# SmartBakerySensor.net
KiCad netlist of a schematic drawn in EAGLE
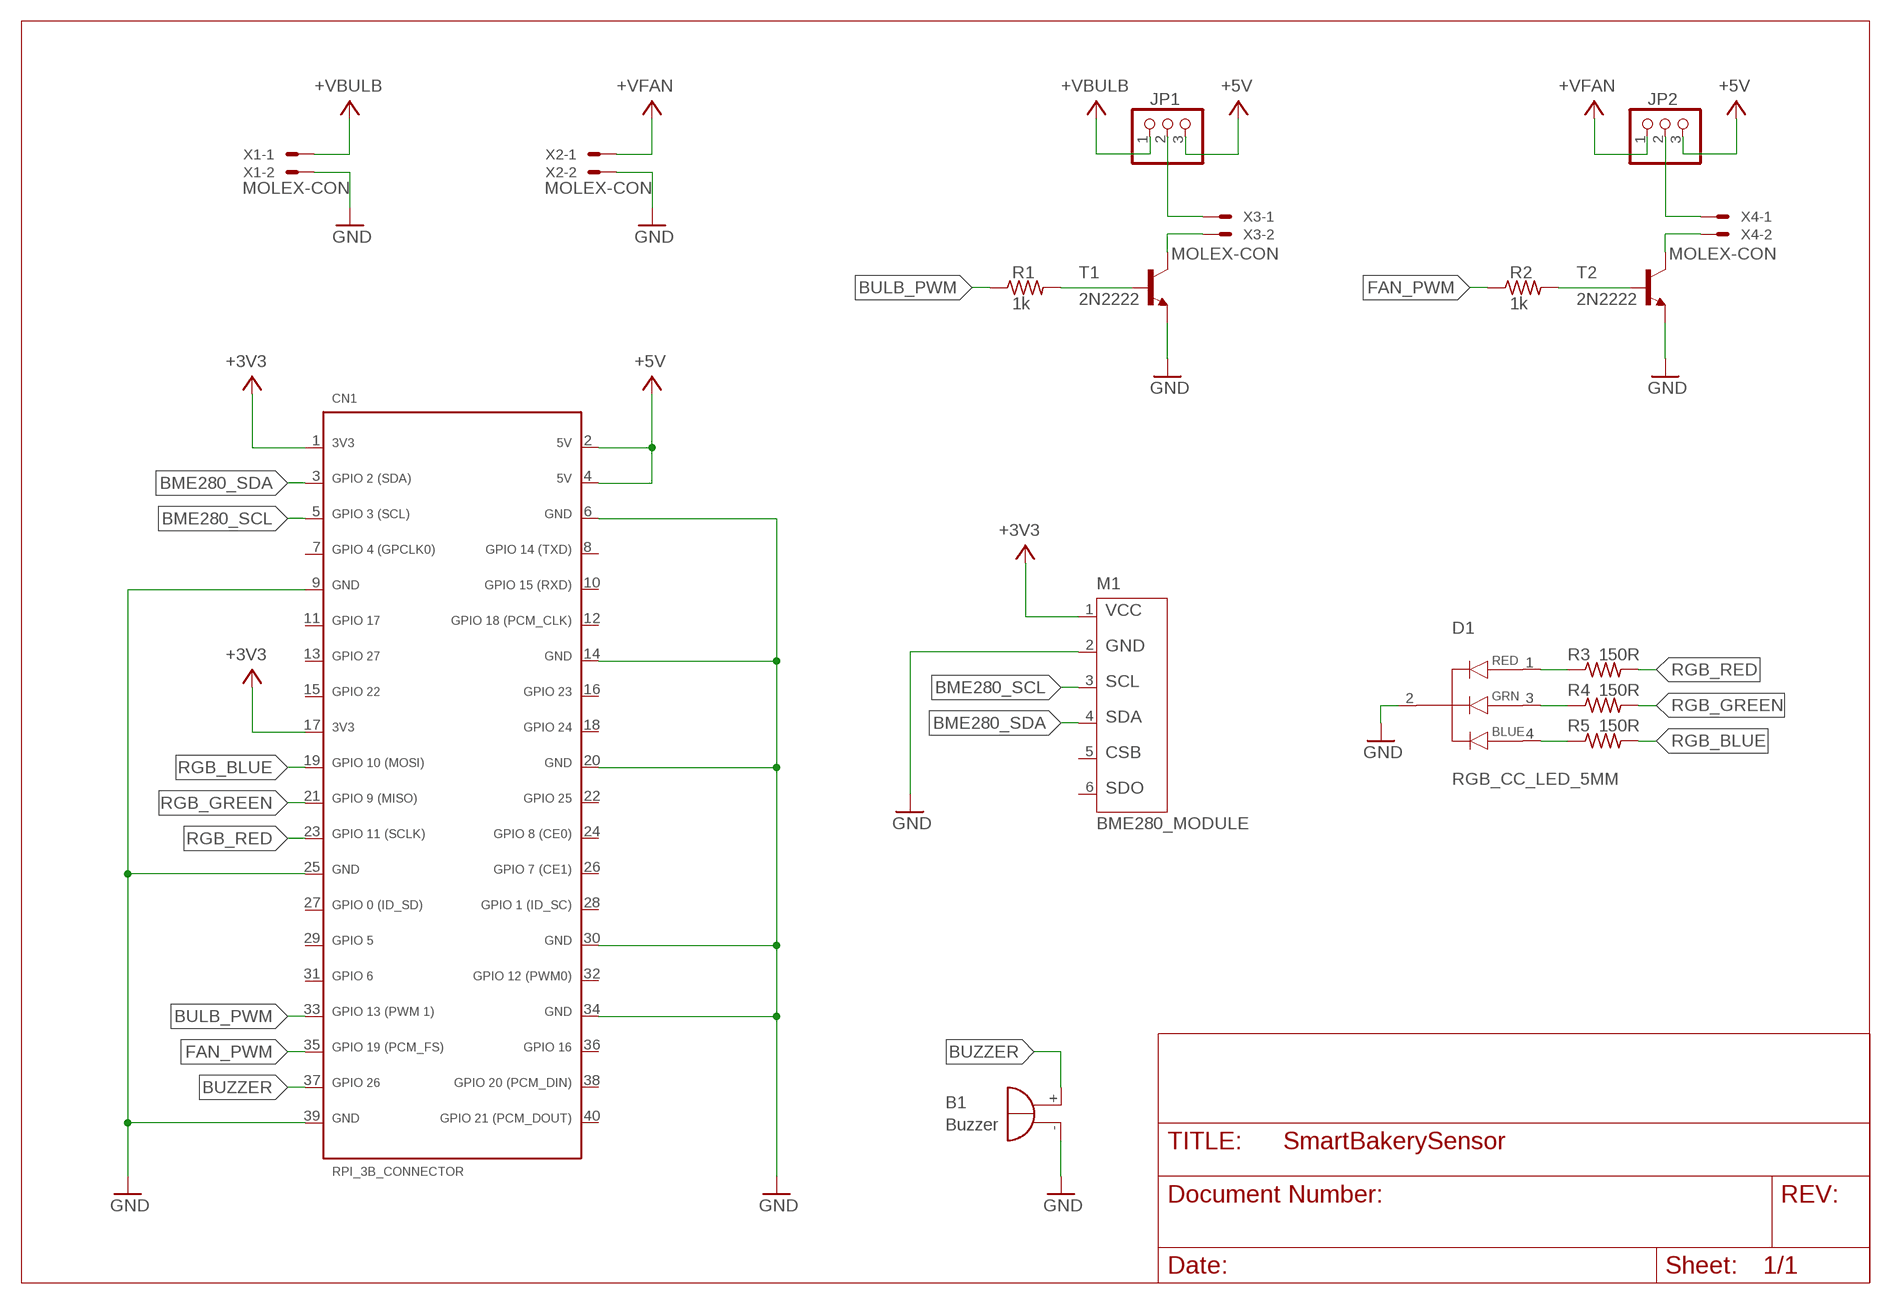
[diagram p0: schematic, sheet 1]

(export (version "E")
  (design (tool "Eeschema 10.0.6"))
  (components
    (comp (ref "B1")
      (value "Buzzer")
      (footprint "eagle-import:F_TMB")
      (libsource (lib "eagle-import") (part "F/TMB"))
    )
    (comp (ref "CN1")
      (value "RPI_3B_CONNECTOR")
      (footprint "eagle-import:RPI_3B_CONNECTOR_FOOTPRINT")
      (libsource (lib "eagle-import") (part "RPI_3B_CONNECTOR"))
    )
    (comp (ref "D1")
      (value "RGB_CC_LED_5MM")
      (footprint "eagle-import:RGB_CC_LED_FOOTPRINT")
      (libsource (lib "eagle-import") (part "RGB_CC_LED_5MM"))
    )
    (comp (ref "JP1")
      (value "PINHD-1X3")
      (footprint "eagle-import:1X03")
      (libsource (lib "eagle-import") (part "PINHD-1X3"))
    )
    (comp (ref "JP2")
      (value "PINHD-1X3")
      (footprint "eagle-import:1X03")
      (libsource (lib "eagle-import") (part "PINHD-1X3"))
    )
    (comp (ref "M1")
      (value "BME280_MODULE")
      (footprint "eagle-import:BME280_FOOTPRINT")
      (libsource (lib "eagle-import") (part "BME280_MODULE"))
    )
    (comp (ref "R1")
      (value "1k")
      (footprint "eagle-import:R0805")
      (libsource (lib "eagle-import") (part "R-US_R0805"))
    )
    (comp (ref "R2")
      (value "1k")
      (footprint "eagle-import:R0805")
      (libsource (lib "eagle-import") (part "R-US_R0805"))
    )
    (comp (ref "R3")
      (value "150R")
      (footprint "eagle-import:R0805")
      (libsource (lib "eagle-import") (part "R-US_R0805"))
    )
    (comp (ref "R4")
      (value "150R")
      (footprint "eagle-import:R0805")
      (libsource (lib "eagle-import") (part "R-US_R0805"))
    )
    (comp (ref "R5")
      (value "150R")
      (footprint "eagle-import:R0805")
      (libsource (lib "eagle-import") (part "R-US_R0805"))
    )
    (comp (ref "T1")
      (value "2N2222")
      (footprint "eagle-import:TO92-EBC")
      (libsource (lib "eagle-import") (part "-NPN-TO92-EBC2N2222"))
    )
    (comp (ref "T2")
      (value "2N2222")
      (footprint "eagle-import:TO92-EBC")
      (libsource (lib "eagle-import") (part "-NPN-TO92-EBC2N2222"))
    )
    (comp (ref "X1")
      (value "MOLEX-CON")
      (footprint "eagle-import:22-23-2021")
      (fields (field (name "MF") "MOLEX") (field (name "MPN") "22-23-2021"))
      (libsource (lib "eagle-import") (part "22-23-2021"))
    )
    (comp (ref "X2")
      (value "MOLEX-CON")
      (footprint "eagle-import:22-23-2021")
      (fields (field (name "MF") "MOLEX") (field (name "MPN") "22-23-2021"))
      (libsource (lib "eagle-import") (part "22-23-2021"))
    )
    (comp (ref "X3")
      (value "MOLEX-CON")
      (footprint "eagle-import:22-23-2021")
      (fields (field (name "MF") "MOLEX") (field (name "MPN") "22-23-2021"))
      (libsource (lib "eagle-import") (part "22-23-2021"))
    )
    (comp (ref "X4")
      (value "MOLEX-CON")
      (footprint "eagle-import:22-23-2021")
      (fields (field (name "MF") "MOLEX") (field (name "MPN") "22-23-2021"))
      (libsource (lib "eagle-import") (part "22-23-2021"))
    )
  )
  (nets
    (net (code "1") (name "+3V3") (class "Default")
      (node (ref "CN1") (pin "1") (pinfunction "1_1") (pintype "bidirectional"))
      (node (ref "CN1") (pin "17") (pinfunction "17_17") (pintype "bidirectional"))
      (node (ref "M1") (pin "1") (pinfunction "1_1") (pintype "bidirectional"))
    )
    (net (code "2") (name "+5V") (class "Default")
      (node (ref "CN1") (pin "2") (pinfunction "2_2") (pintype "bidirectional"))
      (node (ref "CN1") (pin "4") (pinfunction "4_4") (pintype "bidirectional"))
      (node (ref "JP1") (pin "3") (pinfunction "3_3") (pintype "passive"))
      (node (ref "JP2") (pin "3") (pinfunction "3_3") (pintype "passive"))
    )
    (net (code "3") (name "+VBULB") (class "Default")
      (node (ref "JP1") (pin "1") (pinfunction "1_1") (pintype "passive"))
      (node (ref "X1") (pin "1") (pinfunction "S_1") (pintype "passive"))
    )
    (net (code "4") (name "+VFAN") (class "Default")
      (node (ref "JP2") (pin "1") (pinfunction "1_1") (pintype "passive"))
      (node (ref "X2") (pin "1") (pinfunction "S_1") (pintype "passive"))
    )
    (net (code "5") (name "BME280_SCL") (class "Default")
      (node (ref "CN1") (pin "5") (pinfunction "5_5") (pintype "bidirectional"))
      (node (ref "M1") (pin "3") (pinfunction "3_3") (pintype "bidirectional"))
    )
    (net (code "6") (name "BME280_SDA") (class "Default")
      (node (ref "CN1") (pin "3") (pinfunction "3_3") (pintype "bidirectional"))
      (node (ref "M1") (pin "4") (pinfunction "4_4") (pintype "bidirectional"))
    )
    (net (code "7") (name "BULB_PWM") (class "Default")
      (node (ref "CN1") (pin "33") (pinfunction "33_33") (pintype "bidirectional"))
      (node (ref "R1") (pin "1") (pinfunction "1_1") (pintype "passive"))
    )
    (net (code "8") (name "BUZZER") (class "Default")
      (node (ref "B1") (pin "+") (pinfunction "+_+") (pintype "passive"))
      (node (ref "CN1") (pin "37") (pinfunction "37_37") (pintype "bidirectional"))
    )
    (net (code "9") (name "FAN_PWM") (class "Default")
      (node (ref "CN1") (pin "35") (pinfunction "35_35") (pintype "bidirectional"))
      (node (ref "R2") (pin "1") (pinfunction "1_1") (pintype "passive"))
    )
    (net (code "10") (name "GND") (class "Default")
      (node (ref "B1") (pin "-") (pinfunction "-_-") (pintype "passive"))
      (node (ref "CN1") (pin "14") (pinfunction "14_14") (pintype "bidirectional"))
      (node (ref "CN1") (pin "20") (pinfunction "20_20") (pintype "bidirectional"))
      (node (ref "CN1") (pin "25") (pinfunction "25_25") (pintype "bidirectional"))
      (node (ref "CN1") (pin "30") (pinfunction "30_30") (pintype "bidirectional"))
      (node (ref "CN1") (pin "34") (pinfunction "34_34") (pintype "bidirectional"))
      (node (ref "CN1") (pin "39") (pinfunction "39_39") (pintype "bidirectional"))
      (node (ref "CN1") (pin "6") (pinfunction "6_6") (pintype "bidirectional"))
      (node (ref "CN1") (pin "9") (pinfunction "9_9") (pintype "bidirectional"))
      (node (ref "D1") (pin "2") (pinfunction "2_2") (pintype "bidirectional"))
      (node (ref "M1") (pin "2") (pinfunction "2_2") (pintype "bidirectional"))
      (node (ref "T1") (pin "E") (pinfunction "E_E") (pintype "passive"))
      (node (ref "T2") (pin "E") (pinfunction "E_E") (pintype "passive"))
      (node (ref "X1") (pin "2") (pinfunction "S_2") (pintype "passive"))
      (node (ref "X2") (pin "2") (pinfunction "S_2") (pintype "passive"))
    )
    (net (code "11") (name "Net-(D1-Pad1)") (class "Default")
      (node (ref "D1") (pin "1") (pinfunction "1_1") (pintype "bidirectional"))
      (node (ref "R3") (pin "1") (pinfunction "1_1") (pintype "passive"))
    )
    (net (code "12") (name "Net-(D1-Pad3)") (class "Default")
      (node (ref "D1") (pin "3") (pinfunction "3_3") (pintype "bidirectional"))
      (node (ref "R4") (pin "1") (pinfunction "1_1") (pintype "passive"))
    )
    (net (code "13") (name "Net-(D1-Pad4)") (class "Default")
      (node (ref "D1") (pin "4") (pinfunction "4_4") (pintype "bidirectional"))
      (node (ref "R5") (pin "1") (pinfunction "1_1") (pintype "passive"))
    )
    (net (code "14") (name "Net-(R1-Pad2)") (class "Default")
      (node (ref "R1") (pin "2") (pinfunction "2_2") (pintype "passive"))
      (node (ref "T1") (pin "B") (pinfunction "B_B") (pintype "passive"))
    )
    (net (code "15") (name "Net-(R2-Pad2)") (class "Default")
      (node (ref "R2") (pin "2") (pinfunction "2_2") (pintype "passive"))
      (node (ref "T2") (pin "B") (pinfunction "B_B") (pintype "passive"))
    )
    (net (code "16") (name "Net-(X3A-S)") (class "Default")
      (node (ref "JP1") (pin "2") (pinfunction "2_2") (pintype "passive"))
      (node (ref "X3") (pin "1") (pinfunction "S_1") (pintype "passive"))
    )
    (net (code "17") (name "Net-(X3B-S)") (class "Default")
      (node (ref "T1") (pin "C") (pinfunction "C_C") (pintype "passive"))
      (node (ref "X3") (pin "2") (pinfunction "S_2") (pintype "passive"))
    )
    (net (code "18") (name "Net-(X4A-S)") (class "Default")
      (node (ref "JP2") (pin "2") (pinfunction "2_2") (pintype "passive"))
      (node (ref "X4") (pin "1") (pinfunction "S_1") (pintype "passive"))
    )
    (net (code "19") (name "Net-(X4B-S)") (class "Default")
      (node (ref "T2") (pin "C") (pinfunction "C_C") (pintype "passive"))
      (node (ref "X4") (pin "2") (pinfunction "S_2") (pintype "passive"))
    )
    (net (code "20") (name "RGB_BLUE") (class "Default")
      (node (ref "CN1") (pin "19") (pinfunction "19_19") (pintype "bidirectional"))
      (node (ref "R5") (pin "2") (pinfunction "2_2") (pintype "passive"))
    )
    (net (code "21") (name "RGB_GREEN") (class "Default")
      (node (ref "CN1") (pin "21") (pinfunction "21_21") (pintype "bidirectional"))
      (node (ref "R4") (pin "2") (pinfunction "2_2") (pintype "passive"))
    )
    (net (code "22") (name "RGB_RED") (class "Default")
      (node (ref "CN1") (pin "23") (pinfunction "23_23") (pintype "bidirectional"))
      (node (ref "R3") (pin "2") (pinfunction "2_2") (pintype "passive"))
    )
    (net (code "23") (name "unconnected-(CN1-Pad7)") (class "Default")
      (node (ref "CN1") (pin "7") (pinfunction "7_7") (pintype "bidirectional"))
    )
    (net (code "24") (name "unconnected-(CN1-Pad8)") (class "Default")
      (node (ref "CN1") (pin "8") (pinfunction "8_8") (pintype "bidirectional"))
    )
    (net (code "25") (name "unconnected-(CN1-Pad10)") (class "Default")
      (node (ref "CN1") (pin "10") (pinfunction "10_10") (pintype "bidirectional"))
    )
    (net (code "26") (name "unconnected-(CN1-Pad11)") (class "Default")
      (node (ref "CN1") (pin "11") (pinfunction "11_11") (pintype "bidirectional"))
    )
    (net (code "27") (name "unconnected-(CN1-Pad12)") (class "Default")
      (node (ref "CN1") (pin "12") (pinfunction "12_12") (pintype "bidirectional"))
    )
    (net (code "28") (name "unconnected-(CN1-Pad13)") (class "Default")
      (node (ref "CN1") (pin "13") (pinfunction "13_13") (pintype "bidirectional"))
    )
    (net (code "29") (name "unconnected-(CN1-Pad15)") (class "Default")
      (node (ref "CN1") (pin "15") (pinfunction "15_15") (pintype "bidirectional"))
    )
    (net (code "30") (name "unconnected-(CN1-Pad16)") (class "Default")
      (node (ref "CN1") (pin "16") (pinfunction "16_16") (pintype "bidirectional"))
    )
    (net (code "31") (name "unconnected-(CN1-Pad18)") (class "Default")
      (node (ref "CN1") (pin "18") (pinfunction "18_18") (pintype "bidirectional"))
    )
    (net (code "32") (name "unconnected-(CN1-Pad22)") (class "Default")
      (node (ref "CN1") (pin "22") (pinfunction "22_22") (pintype "bidirectional"))
    )
    (net (code "33") (name "unconnected-(CN1-Pad24)") (class "Default")
      (node (ref "CN1") (pin "24") (pinfunction "24_24") (pintype "bidirectional"))
    )
    (net (code "34") (name "unconnected-(CN1-Pad26)") (class "Default")
      (node (ref "CN1") (pin "26") (pinfunction "26_26") (pintype "bidirectional"))
    )
    (net (code "35") (name "unconnected-(CN1-Pad27)") (class "Default")
      (node (ref "CN1") (pin "27") (pinfunction "27_27") (pintype "bidirectional"))
    )
    (net (code "36") (name "unconnected-(CN1-Pad28)") (class "Default")
      (node (ref "CN1") (pin "28") (pinfunction "28_28") (pintype "bidirectional"))
    )
    (net (code "37") (name "unconnected-(CN1-Pad29)") (class "Default")
      (node (ref "CN1") (pin "29") (pinfunction "29_29") (pintype "bidirectional"))
    )
    (net (code "38") (name "unconnected-(CN1-Pad31)") (class "Default")
      (node (ref "CN1") (pin "31") (pinfunction "31_31") (pintype "bidirectional"))
    )
    (net (code "39") (name "unconnected-(CN1-Pad32)") (class "Default")
      (node (ref "CN1") (pin "32") (pinfunction "32_32") (pintype "bidirectional"))
    )
    (net (code "40") (name "unconnected-(CN1-Pad36)") (class "Default")
      (node (ref "CN1") (pin "36") (pinfunction "36_36") (pintype "bidirectional"))
    )
    (net (code "41") (name "unconnected-(CN1-Pad38)") (class "Default")
      (node (ref "CN1") (pin "38") (pinfunction "38_38") (pintype "bidirectional"))
    )
    (net (code "42") (name "unconnected-(CN1-Pad40)") (class "Default")
      (node (ref "CN1") (pin "40") (pinfunction "40_40") (pintype "bidirectional"))
    )
    (net (code "43") (name "unconnected-(M1-Pad5)") (class "Default")
      (node (ref "M1") (pin "5") (pinfunction "5_5") (pintype "bidirectional"))
    )
    (net (code "44") (name "unconnected-(M1-Pad6)") (class "Default")
      (node (ref "M1") (pin "6") (pinfunction "6_6") (pintype "bidirectional"))
    )
  )
)
